# Domino_Di.net
KiCad netlist of a schematic drawn in EAGLE
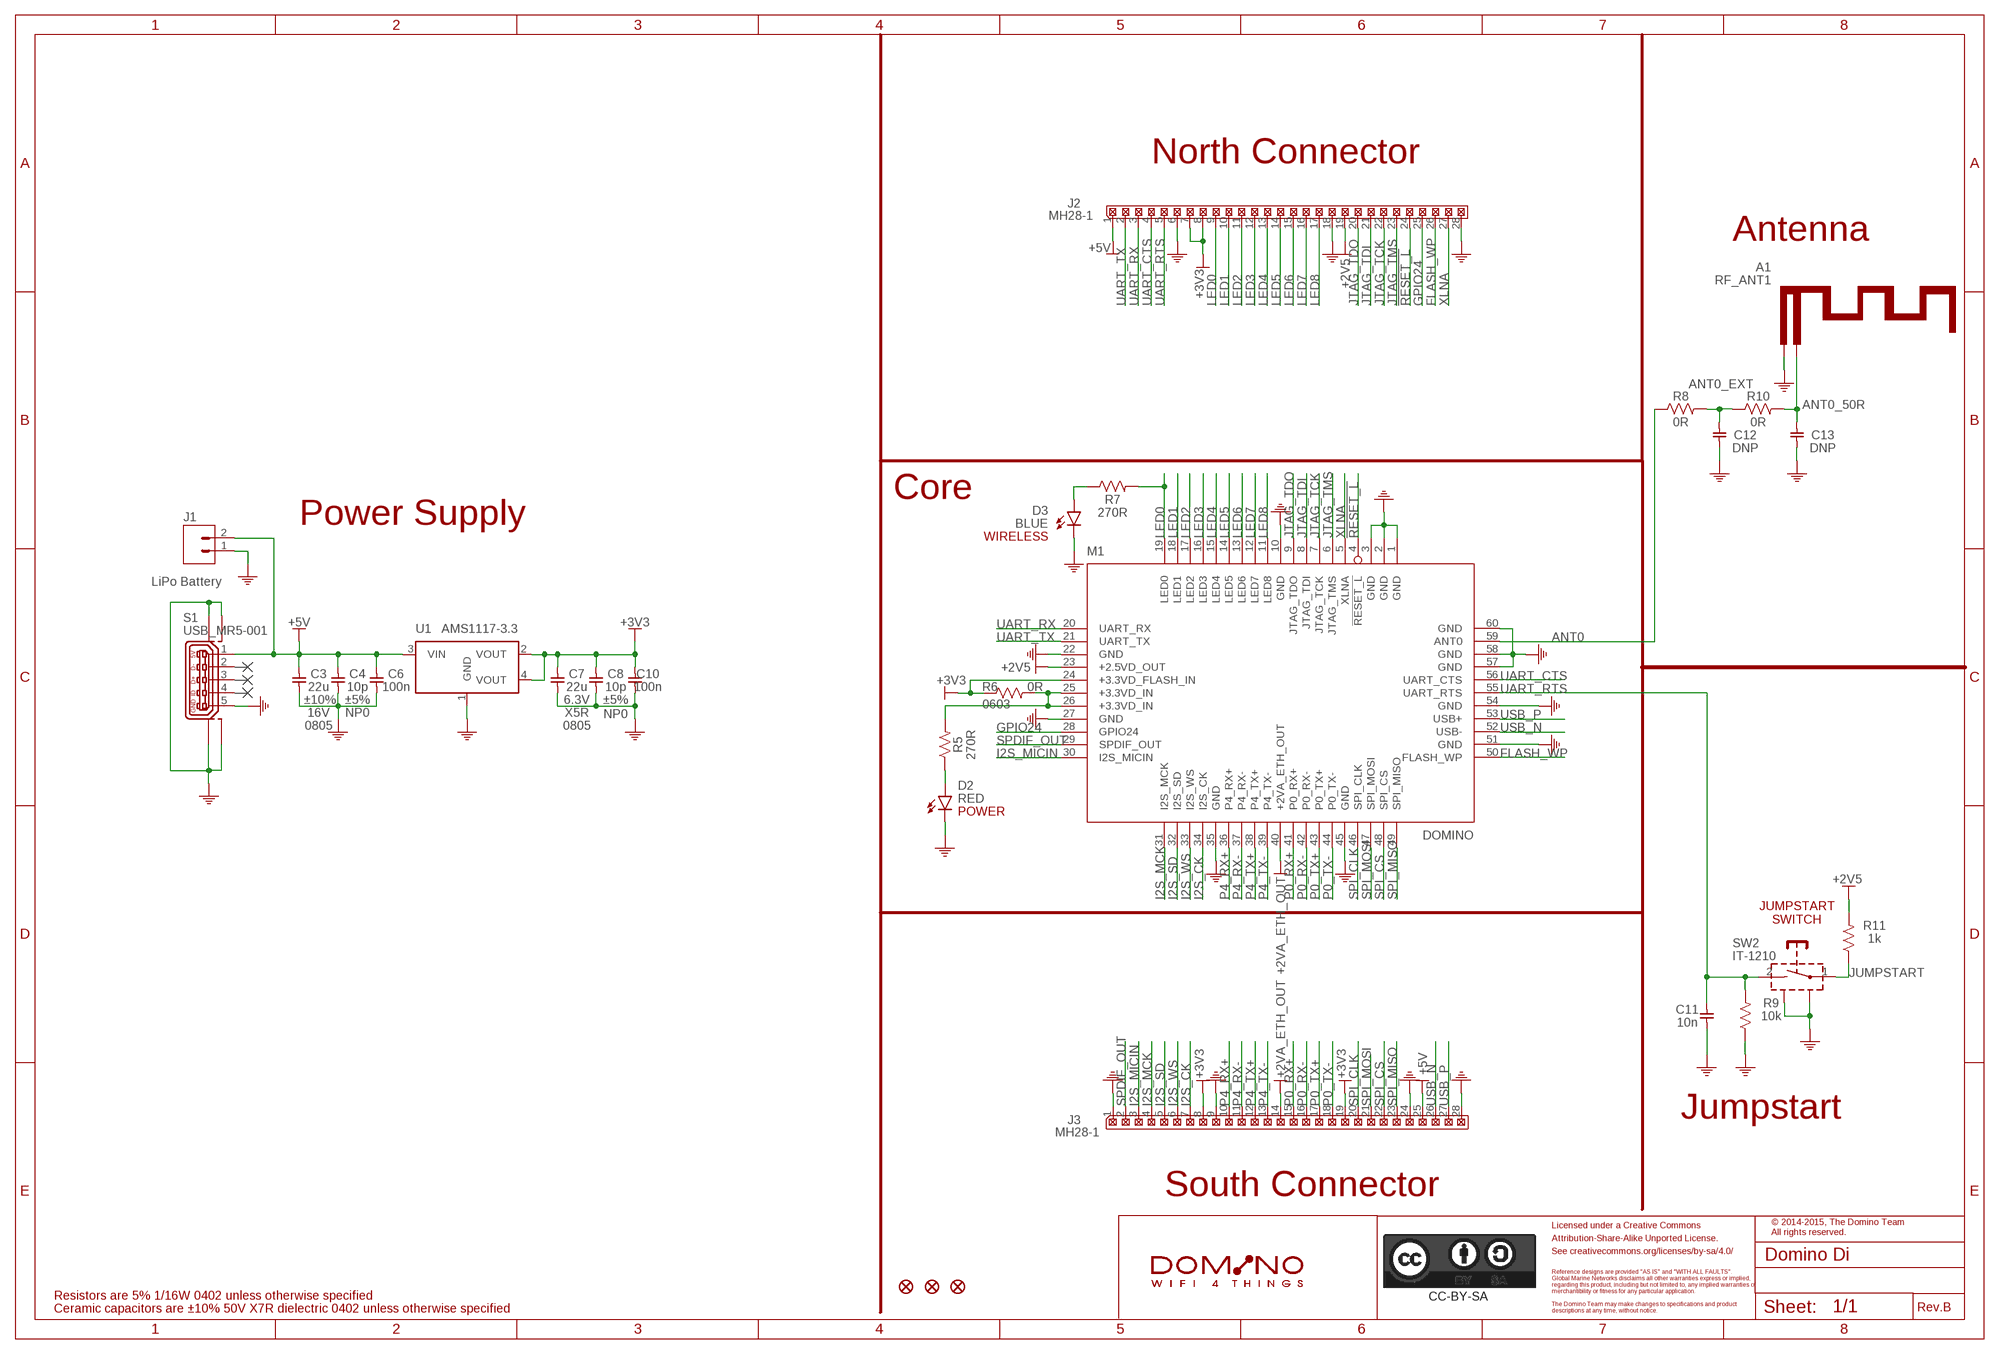
[diagram p0: schematic, sheet 1]

(export (version "E")
  (design (tool "Eeschema 10.0.6"))
  (components
    (comp (ref "A1")
      (value "RF_ANT1")
      (footprint "eagle-import:RF_ANT1")
      (fields (field (name "PARTNO") "WIFI_ANT-2.4GHz"))
      (libsource (lib "eagle-import") (part "RF_ANT1"))
    )
    (comp (ref "C3")
      (value "22u")
      (footprint "eagle-import:C0805")
      (fields
        (field (name "SIZE") "0805")
        (field (name "PARTNO") "C0805_22u_X5R_20%_CER_6V3")
        (field (name "TOL") "±10%")
        (field (name "VOLT") "16V")
      )
      (libsource (lib "eagle-import") (part "CAP_0805"))
    )
    (comp (ref "C4")
      (value "10p")
      (footprint "eagle-import:C0402")
      (fields
        (field (name "PARTNO") "C0402_10p_NP0_5%_CER_50V")
        (field (name "TC") "NP0")
        (field (name "TOL") "±5%")
      )
      (libsource (lib "eagle-import") (part "CAP_0402"))
    )
    (comp (ref "C6")
      (value "100n")
      (footprint "eagle-import:C0402")
      (fields (field (name "PARTNO") "C0402_100n_X7R_10%_CER_50V"))
      (libsource (lib "eagle-import") (part "CAP_0402"))
    )
    (comp (ref "C7")
      (value "22u")
      (footprint "eagle-import:C0805")
      (fields
        (field (name "SIZE") "0805")
        (field (name "PARTNO") "C0805_22u_X5R_20%_CER_6V3")
        (field (name "TC") "X5R")
        (field (name "VOLT") "6.3V")
      )
      (libsource (lib "eagle-import") (part "CAP_0805"))
    )
    (comp (ref "C8")
      (value "10p")
      (footprint "eagle-import:C0402")
      (fields
        (field (name "PARTNO") "C0402_10p_NP0_5%_CER_50V")
        (field (name "TC") "NP0")
        (field (name "TOL") "±5%")
      )
      (libsource (lib "eagle-import") (part "CAP_0402"))
    )
    (comp (ref "C10")
      (value "100n")
      (footprint "eagle-import:C0402")
      (fields (field (name "PARTNO") "C0402_100n_X7R_10%_CER_50V"))
      (libsource (lib "eagle-import") (part "CAP_0402"))
    )
    (comp (ref "C11")
      (value "10n")
      (footprint "eagle-import:C0402")
      (fields (field (name "PARTNO") "C0402_10n_X7R_10%_CER_50V"))
      (libsource (lib "eagle-import") (part "CAP_0402"))
    )
    (comp (ref "C12")
      (value "DNP")
      (footprint "eagle-import:C0402")
      (fields (field (name "PARTNO") "C0402_DNP"))
      (libsource (lib "eagle-import") (part "CAP_0402"))
    )
    (comp (ref "C13")
      (value "DNP")
      (footprint "eagle-import:C0402")
      (fields (field (name "PARTNO") "C0402_DNP"))
      (libsource (lib "eagle-import") (part "CAP_0402"))
    )
    (comp (ref "CC-BY-SA")
      (value "CC-BY-SA_LOGO")
      (footprint "eagle-import:CC-BY-SA_LOGO")
      (libsource (lib "eagle-import") (part "CC-BY-SA_LOGO"))
    )
    (comp (ref "D2")
      (value "RED")
      (footprint "eagle-import:LED0402")
      (fields (field (name "PARTNO") "LED0402-RED"))
      (libsource (lib "eagle-import") (part "LED_0402"))
    )
    (comp (ref "D3")
      (value "BLUE")
      (footprint "eagle-import:LED0402")
      (fields (field (name "PARTNO") "LED0402-BLUE"))
      (libsource (lib "eagle-import") (part "LED_0402"))
    )
    (comp (ref "F1")
      (value "FIDUCIAL")
      (footprint "eagle-import:FIDUCIAL")
      (libsource (lib "eagle-import") (part "FIDUCIAL"))
    )
    (comp (ref "F2")
      (value "FIDUCIAL")
      (footprint "eagle-import:FIDUCIAL")
      (libsource (lib "eagle-import") (part "FIDUCIAL"))
    )
    (comp (ref "F3")
      (value "FIDUCIAL")
      (footprint "eagle-import:FIDUCIAL")
      (libsource (lib "eagle-import") (part "FIDUCIAL"))
    )
    (comp (ref "J1")
      (value "LiPo Battery")
      (footprint "eagle-import:S2B-PH-SM4-TB")
      (fields (field (name "PARTNO") "S2B-PH-SM4-TB"))
      (libsource (lib "eagle-import") (part "SB-PH-?-TBSM42"))
    )
    (comp (ref "J2")
      (value "MH28-1")
      (footprint "eagle-import:MH28-1-0.1")
      (fields (field (name "PARTNO") "MH28-1-0.1"))
      (libsource (lib "eagle-import") (part "MH28-1"))
    )
    (comp (ref "J3")
      (value "MH28-1")
      (footprint "eagle-import:MH28-1-0.1")
      (fields (field (name "PARTNO") "MH28-1-0.1"))
      (libsource (lib "eagle-import") (part "MH28-1"))
    )
    (comp (ref "M1")
      (value "DOMINO")
      (footprint "eagle-import:DOMINO")
      (fields (field (name "PARTNO") "DOMINO-CORE"))
      (libsource (lib "eagle-import") (part "DOMINO"))
    )
    (comp (ref "R5")
      (value "270R")
      (footprint "eagle-import:R0402")
      (fields (field (name "PARTNO") "R0402_270R_5%_62.5mW"))
      (libsource (lib "eagle-import") (part "RES_0402"))
    )
    (comp (ref "R6")
      (value "0R")
      (footprint "eagle-import:R0603")
      (fields (field (name "SIZE") "0603") (field (name "PARTNO") "R0603_0R_5%_125mW"))
      (libsource (lib "eagle-import") (part "RES_0603"))
    )
    (comp (ref "R7")
      (value "270R")
      (footprint "eagle-import:R0402")
      (fields (field (name "PARTNO") "R0402_270R_5%_62.5mW"))
      (libsource (lib "eagle-import") (part "RES_0402"))
    )
    (comp (ref "R8")
      (value "0R")
      (footprint "eagle-import:R0402")
      (fields (field (name "PARTNO") "R0402_0R_5%_62.5mW"))
      (libsource (lib "eagle-import") (part "RES_0402"))
    )
    (comp (ref "R9")
      (value "10k")
      (footprint "eagle-import:R0402")
      (fields (field (name "PARTNO") "R0402_10k_5%_62.5mW"))
      (libsource (lib "eagle-import") (part "RES_0402"))
    )
    (comp (ref "R10")
      (value "0R")
      (footprint "eagle-import:R0402")
      (fields (field (name "PARTNO") "R0402_0R_5%_62.5mW"))
      (libsource (lib "eagle-import") (part "RES_0402"))
    )
    (comp (ref "R11")
      (value "1k")
      (footprint "eagle-import:R0402")
      (fields (field (name "PARTNO") "R0402_1k_5%_62.5mW"))
      (libsource (lib "eagle-import") (part "RES_0402"))
    )
    (comp (ref "S1")
      (value "USB_MR5-001")
      (footprint "eagle-import:USB-MR5-001")
      (fields (field (name "PARTNO") "USB MR5-001"))
      (libsource (lib "eagle-import") (part "USB_MR5-001"))
    )
    (comp (ref "SW2")
      (value "IT-1210")
      (footprint "eagle-import:IT-1210")
      (libsource (lib "eagle-import") (part "IT-1210"))
    )
    (comp (ref "U1")
      (value "AMS1117-3.3")
      (footprint "eagle-import:SOT223")
      (libsource (lib "eagle-import") (part "AMS1117-3.3"))
    )
    (comp (ref "W1")
      (value "DOMINO_LOGO")
      (footprint "eagle-import:DOMINO_LOGO")
      (libsource (lib "eagle-import") (part "DOMINO_LOGO"))
    )
  )
  (nets
    (net (code "1") (name "+2V5") (class "Default")
      (node (ref "J2") (pin "19") (pinfunction "19_19") (pintype "passive"))
      (node (ref "M1") (pin "23") (pinfunction "+2.5VD_OUT_23") (pintype "power_in"))
      (node (ref "R11") (pin "2") (pinfunction "2_2") (pintype "passive"))
    )
    (net (code "2") (name "+2VA_ETH_OUT") (class "Default")
      (node (ref "J3") (pin "14") (pinfunction "14_14") (pintype "passive"))
      (node (ref "M1") (pin "40") (pinfunction "+2VA_ETH_OUT_40") (pintype "power_in"))
    )
    (net (code "3") (name "+3V3") (class "Default")
      (node (ref "C10") (pin "1") (pinfunction "1_1") (pintype "passive"))
      (node (ref "C7") (pin "1") (pinfunction "1_1") (pintype "passive"))
      (node (ref "C8") (pin "1") (pinfunction "1_1") (pintype "passive"))
      (node (ref "J2") (pin "7") (pinfunction "7_7") (pintype "passive"))
      (node (ref "J2") (pin "8") (pinfunction "8_8") (pintype "passive"))
      (node (ref "J3") (pin "19") (pinfunction "19_19") (pintype "passive"))
      (node (ref "J3") (pin "8") (pinfunction "8_8") (pintype "passive"))
      (node (ref "M1") (pin "24") (pinfunction "+3.3VD_FLASH_IN_24") (pintype "power_in"))
      (node (ref "R6") (pin "1") (pinfunction "1_1") (pintype "passive"))
      (node (ref "U1") (pin "2") (pinfunction "VOUT_2") (pintype "power_in"))
      (node (ref "U1") (pin "4") (pinfunction "VOUT_4") (pintype "bidirectional"))
    )
    (net (code "4") (name "+5V") (class "Default")
      (node (ref "C3") (pin "1") (pinfunction "1_1") (pintype "passive"))
      (node (ref "C4") (pin "1") (pinfunction "1_1") (pintype "passive"))
      (node (ref "C6") (pin "1") (pinfunction "1_1") (pintype "passive"))
      (node (ref "J1") (pin "2") (pinfunction "2_2") (pintype "passive"))
      (node (ref "J2") (pin "1") (pinfunction "1_1") (pintype "passive"))
      (node (ref "J3") (pin "25") (pinfunction "25_25") (pintype "passive"))
      (node (ref "S1") (pin "1") (pinfunction "1_1") (pintype "passive"))
      (node (ref "U1") (pin "3") (pinfunction "VIN_3") (pintype "power_in"))
    )
    (net (code "5") (name "/ANT0") (class "Default")
      (node (ref "M1") (pin "59") (pinfunction "ANT0_59") (pintype "passive"))
      (node (ref "R8") (pin "1") (pinfunction "1_1") (pintype "passive"))
    )
    (net (code "6") (name "/ANT0_50R") (class "Default")
      (node (ref "A1") (pin "FEED") (pinfunction "FEED_FEED") (pintype "passive"))
      (node (ref "C13") (pin "1") (pinfunction "1_1") (pintype "passive"))
      (node (ref "R10") (pin "2") (pinfunction "2_2") (pintype "passive"))
    )
    (net (code "7") (name "/ANT0_EXT") (class "Default")
      (node (ref "C12") (pin "1") (pinfunction "1_1") (pintype "passive"))
      (node (ref "R10") (pin "1") (pinfunction "1_1") (pintype "passive"))
      (node (ref "R8") (pin "2") (pinfunction "2_2") (pintype "passive"))
    )
    (net (code "8") (name "/FLASH_WP") (class "Default")
      (node (ref "J2") (pin "26") (pinfunction "26_26") (pintype "passive"))
      (node (ref "M1") (pin "50") (pinfunction "FLASH_WP_50") (pintype "bidirectional"))
    )
    (net (code "9") (name "/GPIO24") (class "Default")
      (node (ref "J2") (pin "25") (pinfunction "25_25") (pintype "passive"))
      (node (ref "M1") (pin "28") (pinfunction "GPIO24_28") (pintype "bidirectional"))
    )
    (net (code "10") (name "/I2S_CK") (class "Default")
      (node (ref "J3") (pin "7") (pinfunction "7_7") (pintype "passive"))
      (node (ref "M1") (pin "34") (pinfunction "I2S_CK_34") (pintype "bidirectional"))
    )
    (net (code "11") (name "/I2S_MCK") (class "Default")
      (node (ref "J3") (pin "4") (pinfunction "4_4") (pintype "passive"))
      (node (ref "M1") (pin "31") (pinfunction "I2S_MCK_31") (pintype "bidirectional"))
    )
    (net (code "12") (name "/I2S_MICIN") (class "Default")
      (node (ref "J3") (pin "3") (pinfunction "3_3") (pintype "passive"))
      (node (ref "M1") (pin "30") (pinfunction "I2S_MICIN_30") (pintype "bidirectional"))
    )
    (net (code "13") (name "/I2S_SD") (class "Default")
      (node (ref "J3") (pin "5") (pinfunction "5_5") (pintype "passive"))
      (node (ref "M1") (pin "32") (pinfunction "I2S_SD_32") (pintype "bidirectional"))
    )
    (net (code "14") (name "/I2S_WS") (class "Default")
      (node (ref "J3") (pin "6") (pinfunction "6_6") (pintype "passive"))
      (node (ref "M1") (pin "33") (pinfunction "I2S_WS_33") (pintype "bidirectional"))
    )
    (net (code "15") (name "/JTAG_TCK") (class "Default")
      (node (ref "J2") (pin "22") (pinfunction "22_22") (pintype "passive"))
      (node (ref "M1") (pin "7") (pinfunction "JTAG_TCK_7") (pintype "bidirectional"))
    )
    (net (code "16") (name "/JTAG_TDI") (class "Default")
      (node (ref "J2") (pin "21") (pinfunction "21_21") (pintype "passive"))
      (node (ref "M1") (pin "8") (pinfunction "JTAG_TDI_8") (pintype "bidirectional"))
    )
    (net (code "17") (name "/JTAG_TDO") (class "Default")
      (node (ref "J2") (pin "20") (pinfunction "20_20") (pintype "passive"))
      (node (ref "M1") (pin "9") (pinfunction "JTAG_TDO_9") (pintype "bidirectional"))
    )
    (net (code "18") (name "/JTAG_TMS") (class "Default")
      (node (ref "J2") (pin "23") (pinfunction "23_23") (pintype "passive"))
      (node (ref "M1") (pin "6") (pinfunction "JTAG_TMS_6") (pintype "bidirectional"))
    )
    (net (code "19") (name "/JUMPSTART") (class "Default")
      (node (ref "R11") (pin "1") (pinfunction "1_1") (pintype "passive"))
      (node (ref "SW2") (pin "1") (pinfunction "1_1") (pintype "passive"))
    )
    (net (code "20") (name "/LED0") (class "Default")
      (node (ref "J2") (pin "9") (pinfunction "9_9") (pintype "passive"))
      (node (ref "M1") (pin "19") (pinfunction "LED0_19") (pintype "bidirectional"))
      (node (ref "R7") (pin "2") (pinfunction "2_2") (pintype "passive"))
    )
    (net (code "21") (name "/LED1") (class "Default")
      (node (ref "J2") (pin "10") (pinfunction "10_10") (pintype "passive"))
      (node (ref "M1") (pin "18") (pinfunction "LED1_18") (pintype "bidirectional"))
    )
    (net (code "22") (name "/LED2") (class "Default")
      (node (ref "J2") (pin "11") (pinfunction "11_11") (pintype "passive"))
      (node (ref "M1") (pin "17") (pinfunction "LED2_17") (pintype "bidirectional"))
    )
    (net (code "23") (name "/LED3") (class "Default")
      (node (ref "J2") (pin "12") (pinfunction "12_12") (pintype "passive"))
      (node (ref "M1") (pin "16") (pinfunction "LED3_16") (pintype "bidirectional"))
    )
    (net (code "24") (name "/LED4") (class "Default")
      (node (ref "J2") (pin "13") (pinfunction "13_13") (pintype "passive"))
      (node (ref "M1") (pin "15") (pinfunction "LED4_15") (pintype "bidirectional"))
    )
    (net (code "25") (name "/LED5") (class "Default")
      (node (ref "J2") (pin "14") (pinfunction "14_14") (pintype "passive"))
      (node (ref "M1") (pin "14") (pinfunction "LED5_14") (pintype "bidirectional"))
    )
    (net (code "26") (name "/LED6") (class "Default")
      (node (ref "J2") (pin "15") (pinfunction "15_15") (pintype "passive"))
      (node (ref "M1") (pin "13") (pinfunction "LED6_13") (pintype "bidirectional"))
    )
    (net (code "27") (name "/LED7") (class "Default")
      (node (ref "J2") (pin "16") (pinfunction "16_16") (pintype "passive"))
      (node (ref "M1") (pin "12") (pinfunction "LED7_12") (pintype "bidirectional"))
    )
    (net (code "28") (name "/LED8") (class "Default")
      (node (ref "J2") (pin "17") (pinfunction "17_17") (pintype "passive"))
      (node (ref "M1") (pin "11") (pinfunction "LED8_11") (pintype "bidirectional"))
    )
    (net (code "29") (name "/P0_RX+") (class "Default")
      (node (ref "J3") (pin "15") (pinfunction "15_15") (pintype "passive"))
      (node (ref "M1") (pin "41") (pinfunction "P0_RX+_41") (pintype "passive"))
    )
    (net (code "30") (name "/P0_RX-") (class "Default")
      (node (ref "J3") (pin "16") (pinfunction "16_16") (pintype "passive"))
      (node (ref "M1") (pin "42") (pinfunction "P0_RX-_42") (pintype "passive"))
    )
    (net (code "31") (name "/P0_TX+") (class "Default")
      (node (ref "J3") (pin "17") (pinfunction "17_17") (pintype "passive"))
      (node (ref "M1") (pin "43") (pinfunction "P0_TX+_43") (pintype "passive"))
    )
    (net (code "32") (name "/P0_TX-") (class "Default")
      (node (ref "J3") (pin "18") (pinfunction "18_18") (pintype "passive"))
      (node (ref "M1") (pin "44") (pinfunction "P0_TX-_44") (pintype "passive"))
    )
    (net (code "33") (name "/P4_RX+") (class "Default")
      (node (ref "J3") (pin "10") (pinfunction "10_10") (pintype "passive"))
      (node (ref "M1") (pin "36") (pinfunction "P4_RX+_36") (pintype "passive"))
    )
    (net (code "34") (name "/P4_RX-") (class "Default")
      (node (ref "J3") (pin "11") (pinfunction "11_11") (pintype "passive"))
      (node (ref "M1") (pin "37") (pinfunction "P4_RX-_37") (pintype "passive"))
    )
    (net (code "35") (name "/P4_TX+") (class "Default")
      (node (ref "J3") (pin "12") (pinfunction "12_12") (pintype "passive"))
      (node (ref "M1") (pin "38") (pinfunction "P4_TX+_38") (pintype "passive"))
    )
    (net (code "36") (name "/P4_TX-") (class "Default")
      (node (ref "J3") (pin "13") (pinfunction "13_13") (pintype "passive"))
      (node (ref "M1") (pin "39") (pinfunction "P4_TX-_39") (pintype "passive"))
    )
    (net (code "37") (name "/SPDIF_OUT") (class "Default")
      (node (ref "J3") (pin "2") (pinfunction "2_2") (pintype "passive"))
      (node (ref "M1") (pin "29") (pinfunction "SPDIF_OUT_29") (pintype "bidirectional"))
    )
    (net (code "38") (name "/SPI_CLK") (class "Default")
      (node (ref "J3") (pin "20") (pinfunction "20_20") (pintype "passive"))
      (node (ref "M1") (pin "46") (pinfunction "SPI_CLK_46") (pintype "bidirectional"))
    )
    (net (code "39") (name "/SPI_CS") (class "Default")
      (node (ref "J3") (pin "22") (pinfunction "22_22") (pintype "passive"))
      (node (ref "M1") (pin "48") (pinfunction "SPI_CS_48") (pintype "bidirectional"))
    )
    (net (code "40") (name "/SPI_MISO") (class "Default")
      (node (ref "J3") (pin "23") (pinfunction "23_23") (pintype "passive"))
      (node (ref "M1") (pin "49") (pinfunction "SPI_MISO_49") (pintype "bidirectional"))
    )
    (net (code "41") (name "/SPI_MOSI") (class "Default")
      (node (ref "J3") (pin "21") (pinfunction "21_21") (pintype "passive"))
      (node (ref "M1") (pin "47") (pinfunction "SPI_MOSI_47") (pintype "bidirectional"))
    )
    (net (code "42") (name "/UART_CTS") (class "Default")
      (node (ref "J2") (pin "4") (pinfunction "4_4") (pintype "passive"))
      (node (ref "M1") (pin "56") (pinfunction "UART_CTS_56") (pintype "bidirectional"))
    )
    (net (code "43") (name "/UART_RTS") (class "Default")
      (node (ref "C11") (pin "1") (pinfunction "1_1") (pintype "passive"))
      (node (ref "J2") (pin "5") (pinfunction "5_5") (pintype "passive"))
      (node (ref "M1") (pin "55") (pinfunction "UART_RTS_55") (pintype "bidirectional"))
      (node (ref "R9") (pin "2") (pinfunction "2_2") (pintype "passive"))
      (node (ref "SW2") (pin "2") (pinfunction "2_2") (pintype "passive"))
    )
    (net (code "44") (name "/UART_RX") (class "Default")
      (node (ref "J2") (pin "3") (pinfunction "3_3") (pintype "passive"))
      (node (ref "M1") (pin "20") (pinfunction "UART_RX_20") (pintype "bidirectional"))
    )
    (net (code "45") (name "/UART_TX") (class "Default")
      (node (ref "J2") (pin "2") (pinfunction "2_2") (pintype "passive"))
      (node (ref "M1") (pin "21") (pinfunction "UART_TX_21") (pintype "bidirectional"))
    )
    (net (code "46") (name "/USB_N") (class "Default")
      (node (ref "J3") (pin "26") (pinfunction "26_26") (pintype "passive"))
      (node (ref "M1") (pin "52") (pinfunction "USB-_52") (pintype "passive"))
    )
    (net (code "47") (name "/USB_P") (class "Default")
      (node (ref "J3") (pin "27") (pinfunction "27_27") (pintype "passive"))
      (node (ref "M1") (pin "53") (pinfunction "USB+_53") (pintype "passive"))
    )
    (net (code "48") (name "/XLNA") (class "Default")
      (node (ref "J2") (pin "27") (pinfunction "27_27") (pintype "passive"))
      (node (ref "M1") (pin "5") (pinfunction "XLNA_5") (pintype "bidirectional"))
    )
    (net (code "49") (name "/~{RESET_L}") (class "Default")
      (node (ref "J2") (pin "24") (pinfunction "24_24") (pintype "passive"))
      (node (ref "M1") (pin "4") (pinfunction "~{RESET_L}_4") (pintype "input"))
    )
    (net (code "50") (name "GND") (class "Default")
      (node (ref "A1") (pin "GND") (pinfunction "GND_GND") (pintype "power_in"))
      (node (ref "C10") (pin "2") (pinfunction "2_2") (pintype "passive"))
      (node (ref "C11") (pin "2") (pinfunction "2_2") (pintype "passive"))
      (node (ref "C12") (pin "2") (pinfunction "2_2") (pintype "passive"))
      (node (ref "C13") (pin "2") (pinfunction "2_2") (pintype "passive"))
      (node (ref "C3") (pin "2") (pinfunction "2_2") (pintype "passive"))
      (node (ref "C4") (pin "2") (pinfunction "2_2") (pintype "passive"))
      (node (ref "C6") (pin "2") (pinfunction "2_2") (pintype "passive"))
      (node (ref "C7") (pin "2") (pinfunction "2_2") (pintype "passive"))
      (node (ref "C8") (pin "2") (pinfunction "2_2") (pintype "passive"))
      (node (ref "D2") (pin "1") (pinfunction "C_1") (pintype "passive"))
      (node (ref "D3") (pin "1") (pinfunction "C_1") (pintype "passive"))
      (node (ref "J1") (pin "1") (pinfunction "1_1") (pintype "passive"))
      (node (ref "J2") (pin "18") (pinfunction "18_18") (pintype "passive"))
      (node (ref "J2") (pin "28") (pinfunction "28_28") (pintype "passive"))
      (node (ref "J2") (pin "6") (pinfunction "6_6") (pintype "passive"))
      (node (ref "J3") (pin "1") (pinfunction "1_1") (pintype "passive"))
      (node (ref "J3") (pin "24") (pinfunction "24_24") (pintype "passive"))
      (node (ref "J3") (pin "28") (pinfunction "28_28") (pintype "passive"))
      (node (ref "J3") (pin "9") (pinfunction "9_9") (pintype "passive"))
      (node (ref "M1") (pin "1") (pinfunction "GND_1") (pintype "power_in"))
      (node (ref "M1") (pin "10") (pinfunction "GND_10") (pintype "power_in"))
      (node (ref "M1") (pin "2") (pinfunction "GND_2") (pintype "power_in"))
      (node (ref "M1") (pin "22") (pinfunction "GND_22") (pintype "power_in"))
      (node (ref "M1") (pin "27") (pinfunction "GND_27") (pintype "power_in"))
      (node (ref "M1") (pin "3") (pinfunction "GND_3") (pintype "power_in"))
      (node (ref "M1") (pin "35") (pinfunction "GND_35") (pintype "power_in"))
      (node (ref "M1") (pin "45") (pinfunction "GND_45") (pintype "power_in"))
      (node (ref "M1") (pin "51") (pinfunction "GND_51") (pintype "power_in"))
      (node (ref "M1") (pin "54") (pinfunction "GND_54") (pintype "power_in"))
      (node (ref "M1") (pin "57") (pinfunction "GND_57") (pintype "power_in"))
      (node (ref "M1") (pin "58") (pinfunction "GND_58") (pintype "power_in"))
      (node (ref "M1") (pin "60") (pinfunction "GND_60") (pintype "power_in"))
      (node (ref "R9") (pin "1") (pinfunction "1_1") (pintype "passive"))
      (node (ref "S1") (pin "5") (pinfunction "5_5") (pintype "passive"))
      (node (ref "S1") (pin "SH$1") (pinfunction "M0_SH$1") (pintype "passive"))
      (node (ref "S1") (pin "SH$2") (pinfunction "M1_SH$2") (pintype "passive"))
      (node (ref "S1") (pin "SH$3") (pinfunction "M2_SH$3") (pintype "passive"))
      (node (ref "S1") (pin "SH$4") (pinfunction "M3_SH$4") (pintype "passive"))
      (node (ref "SW2") (pin "SH$1") (pinfunction "SH$1_SH$1") (pintype "passive"))
      (node (ref "SW2") (pin "SH$2") (pinfunction "SH$2_SH$2") (pintype "passive"))
      (node (ref "U1") (pin "1") (pinfunction "GND_1") (pintype "power_in"))
    )
    (net (code "51") (name "Net-(D2-A)") (class "Default")
      (node (ref "D2") (pin "2") (pinfunction "A_2") (pintype "passive"))
      (node (ref "R5") (pin "1") (pinfunction "1_1") (pintype "passive"))
    )
    (net (code "52") (name "Net-(D3-A)") (class "Default")
      (node (ref "D3") (pin "2") (pinfunction "A_2") (pintype "passive"))
      (node (ref "R7") (pin "1") (pinfunction "1_1") (pintype "passive"))
    )
    (net (code "53") (name "Net-(M1-+3.3VD_IN-Pad25)") (class "Default")
      (node (ref "M1") (pin "25") (pinfunction "+3.3VD_IN_25") (pintype "power_in"))
      (node (ref "M1") (pin "26") (pinfunction "+3.3VD_IN_26") (pintype "power_in"))
      (node (ref "R5") (pin "2") (pinfunction "2_2") (pintype "passive"))
      (node (ref "R6") (pin "2") (pinfunction "2_2") (pintype "passive"))
    )
    (net (code "54") (name "unconnected-(S1-Pad2)") (class "Default")
      (node (ref "S1") (pin "2") (pinfunction "2_2") (pintype "passive"))
    )
    (net (code "55") (name "unconnected-(S1-Pad3)") (class "Default")
      (node (ref "S1") (pin "3") (pinfunction "3_3") (pintype "passive"))
    )
    (net (code "56") (name "unconnected-(S1-Pad4)") (class "Default")
      (node (ref "S1") (pin "4") (pinfunction "4_4") (pintype "passive"))
    )
  )
)
